# Etage1_ok.net
KiCad netlist of a schematic drawn in EAGLE
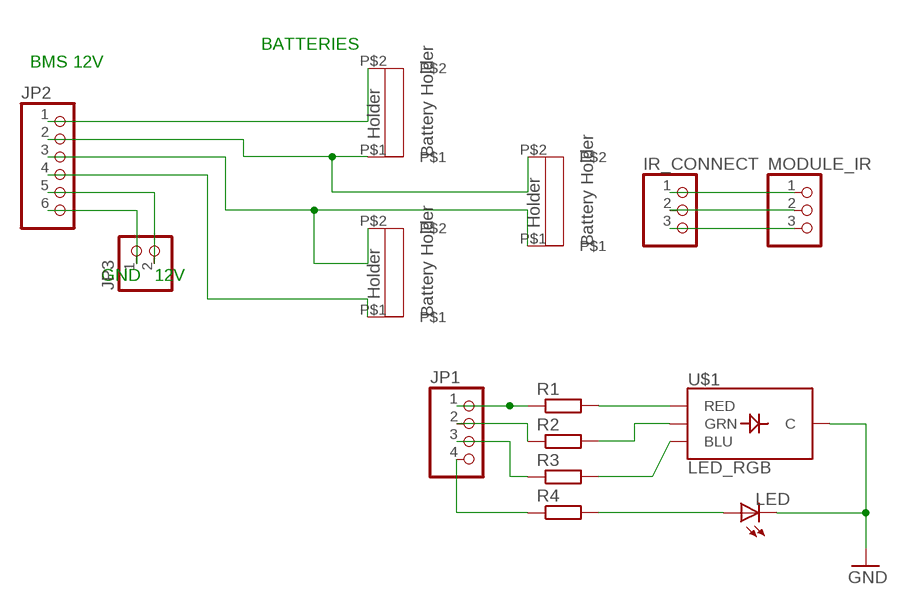
[diagram p0: schematic, sheet 1]

(export (version "E")
  (design (tool "Eeschema 10.0.6"))
  (components
    (comp (ref "IR_CONNECT")
      (value "PINHD-1X3/LONG")
      (footprint "eagle-import:1X03")
      (libsource (lib "eagle-import") (part "PINHD-1X3/LONG"))
    )
    (comp (ref "JP1")
      (value "PINHD-1X4/LONG")
      (footprint "eagle-import:1X04")
      (libsource (lib "eagle-import") (part "PINHD-1X4/LONG"))
    )
    (comp (ref "JP2")
      (value "PINHD-1X6/LONG")
      (footprint "eagle-import:1X06")
      (libsource (lib "eagle-import") (part "PINHD-1X6/LONG"))
    )
    (comp (ref "JP3")
      (value "PINHD-1X2/LONG")
      (footprint "eagle-import:1X02")
      (libsource (lib "eagle-import") (part "PINHD-1X2/LONG"))
    )
    (comp (ref "LED")
      (value "LED5MM")
      (footprint "eagle-import:LED5MM")
      (libsource (lib "eagle-import") (part "LED5MM"))
    )
    (comp (ref "MODULE_IR")
      (value "PINHD-1X3/LONG")
      (footprint "eagle-import:1X03")
      (libsource (lib "eagle-import") (part "PINHD-1X3/LONG"))
    )
    (comp (ref "R1")
      (value "R-EU_0207/10")
      (footprint "eagle-import:0207_10")
      (libsource (lib "eagle-import") (part "R-EU_0207/10"))
    )
    (comp (ref "R2")
      (value "R-EU_0207/10")
      (footprint "eagle-import:0207_10")
      (libsource (lib "eagle-import") (part "R-EU_0207/10"))
    )
    (comp (ref "R3")
      (value "R-EU_0207/10")
      (footprint "eagle-import:0207_10")
      (libsource (lib "eagle-import") (part "R-EU_0207/10"))
    )
    (comp (ref "R4")
      (value "R-EU_0207/10")
      (footprint "eagle-import:0207_10")
      (libsource (lib "eagle-import") (part "R-EU_0207/10"))
    )
    (comp (ref "U$1")
      (value "LED_RGB")
      (footprint "eagle-import:LED-RGB-THRU")
      (libsource (lib "eagle-import") (part "LED_RGB"))
    )
    (comp (ref "U$2")
      (value "SUPPORT_BATTERY")
      (footprint "eagle-import:BATTERY_HOLDER")
      (libsource (lib "eagle-import") (part "SUPPORT_BATTERY"))
    )
    (comp (ref "U$3")
      (value "SUPPORT_BATTERY")
      (footprint "eagle-import:BATTERY_HOLDER")
      (libsource (lib "eagle-import") (part "SUPPORT_BATTERY"))
    )
    (comp (ref "U$4")
      (value "SUPPORT_BATTERY")
      (footprint "eagle-import:BATTERY_HOLDER")
      (libsource (lib "eagle-import") (part "SUPPORT_BATTERY"))
    )
  )
  (nets
    (net (code "1") (name "GND") (class "Default")
      (node (ref "LED") (pin "K") (pinfunction "C_K") (pintype "passive"))
      (node (ref "U$1") (pin "2") (pinfunction "C_2") (pintype "bidirectional"))
    )
    (net (code "2") (name "Net-(IR_CONNECT-Pad1)") (class "Default")
      (node (ref "IR_CONNECT") (pin "1") (pinfunction "1_1") (pintype "passive"))
      (node (ref "MODULE_IR") (pin "1") (pinfunction "1_1") (pintype "passive"))
    )
    (net (code "3") (name "Net-(IR_CONNECT-Pad2)") (class "Default")
      (node (ref "IR_CONNECT") (pin "2") (pinfunction "2_2") (pintype "passive"))
      (node (ref "MODULE_IR") (pin "2") (pinfunction "2_2") (pintype "passive"))
    )
    (net (code "4") (name "Net-(IR_CONNECT-Pad3)") (class "Default")
      (node (ref "IR_CONNECT") (pin "3") (pinfunction "3_3") (pintype "passive"))
      (node (ref "MODULE_IR") (pin "3") (pinfunction "3_3") (pintype "passive"))
    )
    (net (code "5") (name "Net-(JP1-Pad1)") (class "Default")
      (node (ref "JP1") (pin "1") (pinfunction "1_1") (pintype "passive"))
      (node (ref "R1") (pin "1") (pinfunction "1_1") (pintype "passive"))
    )
    (net (code "6") (name "Net-(JP1-Pad2)") (class "Default")
      (node (ref "JP1") (pin "2") (pinfunction "2_2") (pintype "passive"))
      (node (ref "R2") (pin "1") (pinfunction "1_1") (pintype "passive"))
    )
    (net (code "7") (name "Net-(JP1-Pad3)") (class "Default")
      (node (ref "JP1") (pin "3") (pinfunction "3_3") (pintype "passive"))
      (node (ref "R3") (pin "1") (pinfunction "1_1") (pintype "passive"))
    )
    (net (code "8") (name "Net-(JP1-Pad4)") (class "Default")
      (node (ref "JP1") (pin "4") (pinfunction "4_4") (pintype "passive"))
      (node (ref "R4") (pin "1") (pinfunction "1_1") (pintype "passive"))
    )
    (net (code "9") (name "Net-(JP2-Pad1)") (class "Default")
      (node (ref "JP2") (pin "1") (pinfunction "1_1") (pintype "passive"))
      (node (ref "U$4") (pin "P$2") (pinfunction "P$2_P$2") (pintype "bidirectional"))
    )
    (net (code "10") (name "Net-(JP2-Pad2)") (class "Default")
      (node (ref "JP2") (pin "2") (pinfunction "2_2") (pintype "passive"))
      (node (ref "U$2") (pin "P$2") (pinfunction "P$2_P$2") (pintype "bidirectional"))
      (node (ref "U$4") (pin "P$1") (pinfunction "P$1_P$1") (pintype "bidirectional"))
    )
    (net (code "11") (name "Net-(JP2-Pad3)") (class "Default")
      (node (ref "JP2") (pin "3") (pinfunction "3_3") (pintype "passive"))
      (node (ref "U$2") (pin "P$1") (pinfunction "P$1_P$1") (pintype "bidirectional"))
      (node (ref "U$3") (pin "P$2") (pinfunction "P$2_P$2") (pintype "bidirectional"))
    )
    (net (code "12") (name "Net-(JP2-Pad4)") (class "Default")
      (node (ref "JP2") (pin "4") (pinfunction "4_4") (pintype "passive"))
      (node (ref "U$3") (pin "P$1") (pinfunction "P$1_P$1") (pintype "bidirectional"))
    )
    (net (code "13") (name "Net-(JP2-Pad5)") (class "Default")
      (node (ref "JP2") (pin "5") (pinfunction "5_5") (pintype "passive"))
      (node (ref "JP3") (pin "2") (pinfunction "2_2") (pintype "passive"))
    )
    (net (code "14") (name "Net-(JP2-Pad6)") (class "Default")
      (node (ref "JP2") (pin "6") (pinfunction "6_6") (pintype "passive"))
      (node (ref "JP3") (pin "1") (pinfunction "1_1") (pintype "passive"))
    )
    (net (code "15") (name "Net-(LED-PadA)") (class "Default")
      (node (ref "LED") (pin "A") (pinfunction "A_A") (pintype "passive"))
      (node (ref "R4") (pin "2") (pinfunction "2_2") (pintype "passive"))
    )
    (net (code "16") (name "Net-(U$1-BLU)") (class "Default")
      (node (ref "R3") (pin "2") (pinfunction "2_2") (pintype "passive"))
      (node (ref "U$1") (pin "1") (pinfunction "BLU_1") (pintype "bidirectional"))
    )
    (net (code "17") (name "Net-(U$1-GRN)") (class "Default")
      (node (ref "R2") (pin "2") (pinfunction "2_2") (pintype "passive"))
      (node (ref "U$1") (pin "3") (pinfunction "GRN_3") (pintype "bidirectional"))
    )
    (net (code "18") (name "Net-(U$1-RED)") (class "Default")
      (node (ref "R1") (pin "2") (pinfunction "2_2") (pintype "passive"))
      (node (ref "U$1") (pin "4") (pinfunction "RED_4") (pintype "bidirectional"))
    )
  )
)
